# Clock.net
KiCad netlist of a schematic drawn in EAGLE
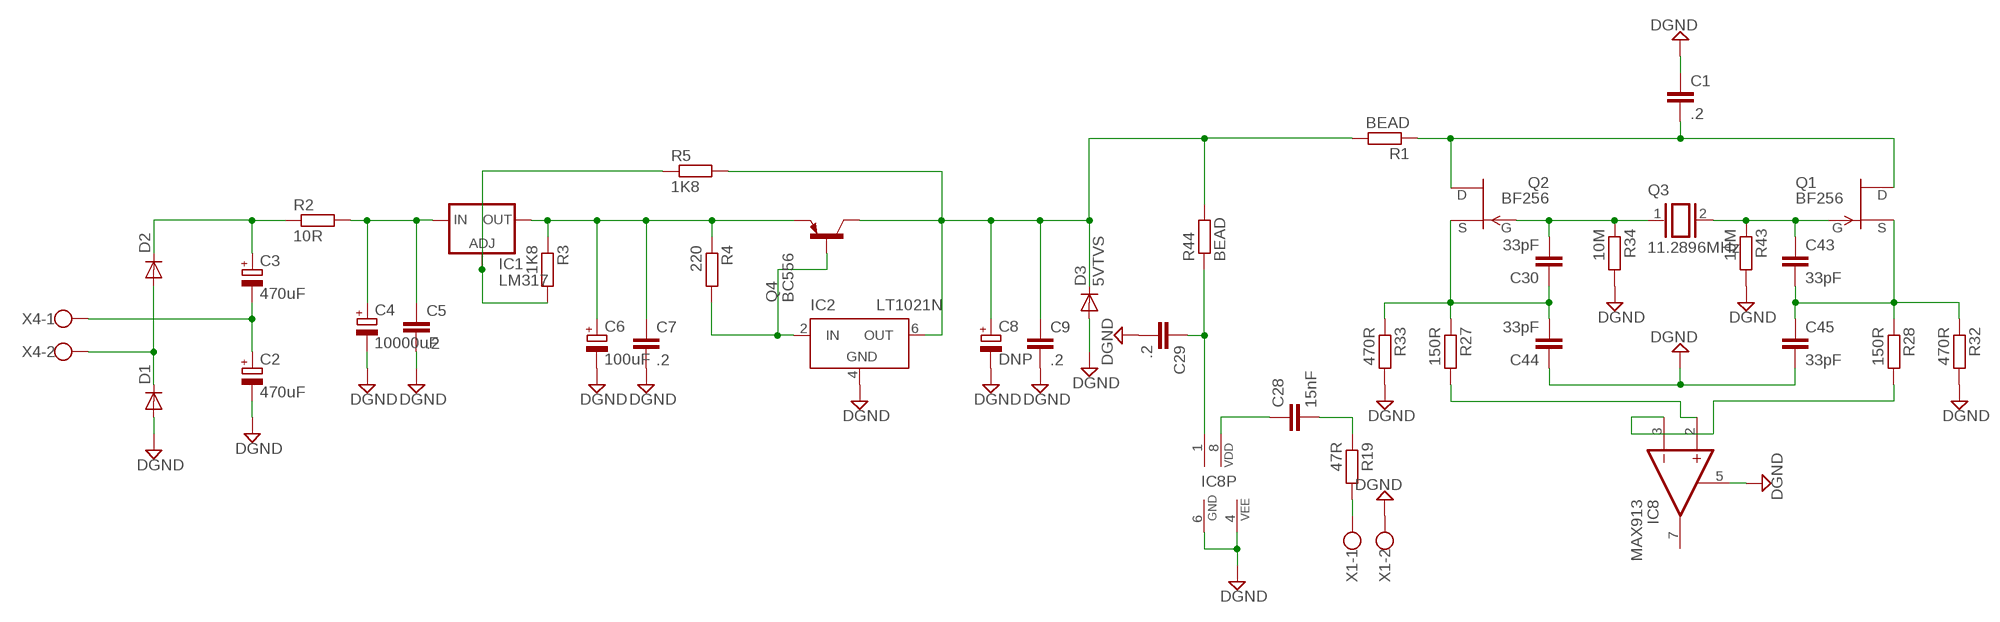
[diagram p0: schematic, sheet 1]

(export (version "E")
  (design (tool "Eeschema 10.0.6"))
  (components
    (comp (ref "C1")
      (value ".2")
      (footprint "eagle-import:C1210K")
      (libsource (lib "eagle-import") (part "C-EUC1210K"))
    )
    (comp (ref "C2")
      (value "470uF")
      (footprint "eagle-import:E5-10,5")
      (libsource (lib "eagle-import") (part "CPOL-EUE5-10.5"))
    )
    (comp (ref "C3")
      (value "470uF")
      (footprint "eagle-import:E5-10,5")
      (libsource (lib "eagle-import") (part "CPOL-EUE5-10.5"))
    )
    (comp (ref "C4")
      (value "10000uF")
      (footprint "eagle-import:E7,5-16")
      (libsource (lib "eagle-import") (part "CPOL-EUE7.5-16"))
    )
    (comp (ref "C5")
      (value ".2")
      (footprint "eagle-import:C1210K")
      (libsource (lib "eagle-import") (part "C-EUC1210K"))
    )
    (comp (ref "C6")
      (value "100uF")
      (footprint "eagle-import:E3,5-8")
      (libsource (lib "eagle-import") (part "CPOL-EUE3.5-8"))
    )
    (comp (ref "C7")
      (value ".2")
      (footprint "eagle-import:C1210K")
      (libsource (lib "eagle-import") (part "C-EUC1210K"))
    )
    (comp (ref "C8")
      (value "DNP")
      (footprint "eagle-import:E3,5-8")
      (libsource (lib "eagle-import") (part "CPOL-EUE3.5-8"))
    )
    (comp (ref "C9")
      (value ".2")
      (footprint "eagle-import:C1210K")
      (libsource (lib "eagle-import") (part "C-EUC1210K"))
    )
    (comp (ref "C28")
      (value "15nF")
      (footprint "eagle-import:C050-055X075")
      (libsource (lib "eagle-import") (part "C-EU050-055X075"))
    )
    (comp (ref "C29")
      (value ".2")
      (footprint "eagle-import:C1210K")
      (libsource (lib "eagle-import") (part "C-EUC1210K"))
    )
    (comp (ref "C30")
      (value "33pF")
      (footprint "eagle-import:C050-030X075")
      (libsource (lib "eagle-import") (part "C-EU050-030X075"))
    )
    (comp (ref "C43")
      (value "33pF")
      (footprint "eagle-import:C050-030X075")
      (libsource (lib "eagle-import") (part "C-EU050-030X075"))
    )
    (comp (ref "C44")
      (value "33pF")
      (footprint "eagle-import:C050-030X075")
      (libsource (lib "eagle-import") (part "C-EU050-030X075"))
    )
    (comp (ref "C45")
      (value "33pF")
      (footprint "eagle-import:C050-030X075")
      (libsource (lib "eagle-import") (part "C-EU050-030X075"))
    )
    (comp (ref "D1")
      (value "1N4148DO35-7")
      (footprint "eagle-import:DO35-7")
      (libsource (lib "eagle-import") (part "1N4148DO35-7"))
    )
    (comp (ref "D2")
      (value "1N4148DO35-7")
      (footprint "eagle-import:DO35-7")
      (libsource (lib "eagle-import") (part "1N4148DO35-7"))
    )
    (comp (ref "D3")
      (value "5VTVS")
      (footprint "eagle-import:DO204-10")
      (libsource (lib "eagle-import") (part "A114"))
    )
    (comp (ref "IC1")
      (value "LM317")
      (footprint "eagle-import:317TS")
      (libsource (lib "eagle-import") (part "LM317TS"))
    )
    (comp (ref "IC2")
      (value "LT1021N")
      (footprint "eagle-import:DIL08")
      (libsource (lib "eagle-import") (part "LT1021N"))
    )
    (comp (ref "IC8")
      (value "MAX913")
      (footprint "eagle-import:DIL08")
      (libsource (lib "eagle-import") (part "MAX903CPA"))
    )
    (comp (ref "Q1")
      (value "BF256")
      (footprint "eagle-import:TO92-")
      (libsource (lib "eagle-import") (part "?5482N4"))
    )
    (comp (ref "Q2")
      (value "BF256")
      (footprint "eagle-import:TO92-")
      (libsource (lib "eagle-import") (part "?5482N4"))
    )
    (comp (ref "Q3")
      (value "11.2896MHz")
      (footprint "eagle-import:QS")
      (libsource (lib "eagle-import") (part "XTAL/S"))
    )
    (comp (ref "Q4")
      (value "BC556")
      (footprint "eagle-import:TO92-EBC")
      (libsource (lib "eagle-import") (part "BC556"))
    )
    (comp (ref "R1")
      (value "BEAD")
      (footprint "eagle-import:R1210")
      (libsource (lib "eagle-import") (part "R-EU_R1210"))
    )
    (comp (ref "R2")
      (value "10R")
      (footprint "eagle-import:0207_10")
      (libsource (lib "eagle-import") (part "R-EU_0207/10"))
    )
    (comp (ref "R3")
      (value "1K8")
      (footprint "eagle-import:0204_7")
      (libsource (lib "eagle-import") (part "R-EU_0204/7"))
    )
    (comp (ref "R4")
      (value "220")
      (footprint "eagle-import:0204_7")
      (libsource (lib "eagle-import") (part "R-EU_0204/7"))
    )
    (comp (ref "R5")
      (value "1K8")
      (footprint "eagle-import:0204_7")
      (libsource (lib "eagle-import") (part "R-EU_0204/7"))
    )
    (comp (ref "R19")
      (value "47R")
      (footprint "eagle-import:R1210")
      (libsource (lib "eagle-import") (part "R-EU_R1210"))
    )
    (comp (ref "R27")
      (value "150R")
      (footprint "eagle-import:0204_7")
      (libsource (lib "eagle-import") (part "R-EU_0204/7"))
    )
    (comp (ref "R28")
      (value "150R")
      (footprint "eagle-import:0204_7")
      (libsource (lib "eagle-import") (part "R-EU_0204/7"))
    )
    (comp (ref "R32")
      (value "470R")
      (footprint "eagle-import:0204_7")
      (libsource (lib "eagle-import") (part "R-EU_0204/7"))
    )
    (comp (ref "R33")
      (value "470R")
      (footprint "eagle-import:0204_7")
      (libsource (lib "eagle-import") (part "R-EU_0204/7"))
    )
    (comp (ref "R34")
      (value "10M")
      (footprint "eagle-import:0204_7")
      (libsource (lib "eagle-import") (part "R-EU_0204/7"))
    )
    (comp (ref "R43")
      (value "10M")
      (footprint "eagle-import:0204_7")
      (libsource (lib "eagle-import") (part "R-EU_0204/7"))
    )
    (comp (ref "R44")
      (value "BEAD")
      (footprint "eagle-import:R1210")
      (libsource (lib "eagle-import") (part "R-EU_R1210"))
    )
    (comp (ref "X1")
      (value "W237-02P")
      (footprint "eagle-import:W237-132")
      (libsource (lib "eagle-import") (part "W237-02P"))
    )
    (comp (ref "X4")
      (value "W237-02P")
      (footprint "eagle-import:W237-132")
      (libsource (lib "eagle-import") (part "W237-02P"))
    )
  )
  (nets
    (net (code "1") (name "DGND") (class "Default")
      (node (ref "C1") (pin "1") (pinfunction "1_1") (pintype "passive"))
      (node (ref "C2") (pin "-") (pinfunction "-_-") (pintype "passive"))
      (node (ref "C29") (pin "2") (pinfunction "2_2") (pintype "passive"))
      (node (ref "C4") (pin "-") (pinfunction "-_-") (pintype "passive"))
      (node (ref "C44") (pin "1") (pinfunction "1_1") (pintype "passive"))
      (node (ref "C45") (pin "2") (pinfunction "2_2") (pintype "passive"))
      (node (ref "C5") (pin "2") (pinfunction "2_2") (pintype "passive"))
      (node (ref "C6") (pin "-") (pinfunction "-_-") (pintype "passive"))
      (node (ref "C7") (pin "2") (pinfunction "2_2") (pintype "passive"))
      (node (ref "C8") (pin "-") (pinfunction "-_-") (pintype "passive"))
      (node (ref "C9") (pin "2") (pinfunction "2_2") (pintype "passive"))
      (node (ref "D1") (pin "A") (pinfunction "A_A") (pintype "passive"))
      (node (ref "D3") (pin "A") (pinfunction "A_A") (pintype "passive"))
      (node (ref "IC2") (pin "4") (pinfunction "GND_4") (pintype "power_in"))
      (node (ref "IC8") (pin "4") (pinfunction "VEE_4") (pintype "power_in"))
      (node (ref "IC8") (pin "5") (pinfunction "LATCH_5") (pintype "passive"))
      (node (ref "IC8") (pin "6") (pinfunction "GND_6") (pintype "power_in"))
      (node (ref "R32") (pin "2") (pinfunction "2_2") (pintype "passive"))
      (node (ref "R33") (pin "2") (pinfunction "2_2") (pintype "passive"))
      (node (ref "R34") (pin "2") (pinfunction "2_2") (pintype "passive"))
      (node (ref "R43") (pin "2") (pinfunction "2_2") (pintype "passive"))
      (node (ref "X1") (pin "2") (pinfunction "KL_2") (pintype "passive"))
    )
    (net (code "2") (name "Net-(C3-Pad+)") (class "Default")
      (node (ref "C3") (pin "+") (pinfunction "+_+") (pintype "passive"))
      (node (ref "D2") (pin "C") (pinfunction "C_C") (pintype "passive"))
      (node (ref "R2") (pin "1") (pinfunction "1_1") (pintype "passive"))
    )
    (net (code "3") (name "Net-(C28-Pad2)") (class "Default")
      (node (ref "C28") (pin "2") (pinfunction "2_2") (pintype "passive"))
      (node (ref "R19") (pin "1") (pinfunction "1_1") (pintype "passive"))
    )
    (net (code "4") (name "Net-(IC1-ADJ)") (class "Default")
      (node (ref "IC1") (pin "1") (pinfunction "ADJ_1") (pintype "input"))
      (node (ref "R3") (pin "2") (pinfunction "2_2") (pintype "passive"))
      (node (ref "R5") (pin "1") (pinfunction "1_1") (pintype "passive"))
    )
    (net (code "5") (name "Net-(IC1-IN)") (class "Default")
      (node (ref "C4") (pin "+") (pinfunction "+_+") (pintype "passive"))
      (node (ref "C5") (pin "1") (pinfunction "1_1") (pintype "passive"))
      (node (ref "IC1") (pin "3") (pinfunction "IN_3") (pintype "input"))
      (node (ref "R2") (pin "2") (pinfunction "2_2") (pintype "passive"))
    )
    (net (code "6") (name "Net-(IC1-OUT)") (class "Default")
      (node (ref "C6") (pin "+") (pinfunction "+_+") (pintype "passive"))
      (node (ref "C7") (pin "1") (pinfunction "1_1") (pintype "passive"))
      (node (ref "IC1") (pin "2") (pinfunction "OUT_2") (pintype "passive"))
      (node (ref "Q4") (pin "E") (pinfunction "E_E") (pintype "passive"))
      (node (ref "R3") (pin "1") (pinfunction "1_1") (pintype "passive"))
      (node (ref "R4") (pin "1") (pinfunction "1_1") (pintype "passive"))
    )
    (net (code "7") (name "Net-(IC2-IN)") (class "Default")
      (node (ref "IC2") (pin "2") (pinfunction "IN_2") (pintype "input"))
      (node (ref "Q4") (pin "B") (pinfunction "B_B") (pintype "passive"))
      (node (ref "R4") (pin "2") (pinfunction "2_2") (pintype "passive"))
    )
    (net (code "8") (name "Net-(IC2-OUT)") (class "Default")
      (node (ref "C8") (pin "+") (pinfunction "+_+") (pintype "passive"))
      (node (ref "C9") (pin "1") (pinfunction "1_1") (pintype "passive"))
      (node (ref "D3") (pin "C") (pinfunction "C_C") (pintype "passive"))
      (node (ref "IC2") (pin "6") (pinfunction "OUT_6") (pintype "output"))
      (node (ref "Q4") (pin "C") (pinfunction "C_C") (pintype "passive"))
      (node (ref "R1") (pin "2") (pinfunction "2_2") (pintype "passive"))
      (node (ref "R44") (pin "2") (pinfunction "2_2") (pintype "passive"))
      (node (ref "R5") (pin "2") (pinfunction "2_2") (pintype "passive"))
    )
    (net (code "9") (name "Net-(IC8A-+IN)") (class "Default")
      (node (ref "IC8") (pin "2") (pinfunction "+IN_2") (pintype "input"))
      (node (ref "R27") (pin "2") (pinfunction "2_2") (pintype "passive"))
    )
    (net (code "10") (name "Net-(IC8A--IN)") (class "Default")
      (node (ref "IC8") (pin "3") (pinfunction "-IN_3") (pintype "input"))
      (node (ref "R28") (pin "2") (pinfunction "2_2") (pintype "passive"))
    )
    (net (code "11") (name "Net-(IC8B-VCC)") (class "Default")
      (node (ref "C29") (pin "1") (pinfunction "1_1") (pintype "passive"))
      (node (ref "IC8") (pin "1") (pinfunction "VCC_1") (pintype "power_in"))
      (node (ref "R44") (pin "1") (pinfunction "1_1") (pintype "passive"))
    )
    (net (code "12") (name "Net-(IC8B-VDD)") (class "Default")
      (node (ref "C28") (pin "1") (pinfunction "1_1") (pintype "passive"))
      (node (ref "IC8") (pin "8") (pinfunction "VDD_8") (pintype "power_in"))
    )
    (net (code "13") (name "Net-(Q1-D)") (class "Default")
      (node (ref "C1") (pin "2") (pinfunction "2_2") (pintype "passive"))
      (node (ref "Q1") (pin "3") (pinfunction "D_3") (pintype "passive"))
      (node (ref "Q2") (pin "3") (pinfunction "D_3") (pintype "passive"))
      (node (ref "R1") (pin "1") (pinfunction "1_1") (pintype "passive"))
    )
    (net (code "14") (name "Net-(Q1-G)") (class "Default")
      (node (ref "C43") (pin "1") (pinfunction "1_1") (pintype "passive"))
      (node (ref "Q1") (pin "1") (pinfunction "G_1") (pintype "passive"))
      (node (ref "Q3") (pin "2") (pinfunction "2_2") (pintype "passive"))
      (node (ref "R43") (pin "1") (pinfunction "1_1") (pintype "passive"))
    )
    (net (code "15") (name "Net-(Q1-S)") (class "Default")
      (node (ref "C43") (pin "2") (pinfunction "2_2") (pintype "passive"))
      (node (ref "C45") (pin "1") (pinfunction "1_1") (pintype "passive"))
      (node (ref "Q1") (pin "2") (pinfunction "S_2") (pintype "passive"))
      (node (ref "R28") (pin "1") (pinfunction "1_1") (pintype "passive"))
      (node (ref "R32") (pin "1") (pinfunction "1_1") (pintype "passive"))
    )
    (net (code "16") (name "Net-(Q2-G)") (class "Default")
      (node (ref "C30") (pin "2") (pinfunction "2_2") (pintype "passive"))
      (node (ref "Q2") (pin "1") (pinfunction "G_1") (pintype "passive"))
      (node (ref "Q3") (pin "1") (pinfunction "1_1") (pintype "passive"))
      (node (ref "R34") (pin "1") (pinfunction "1_1") (pintype "passive"))
    )
    (net (code "17") (name "Net-(Q2-S)") (class "Default")
      (node (ref "C30") (pin "1") (pinfunction "1_1") (pintype "passive"))
      (node (ref "C44") (pin "2") (pinfunction "2_2") (pintype "passive"))
      (node (ref "Q2") (pin "2") (pinfunction "S_2") (pintype "passive"))
      (node (ref "R27") (pin "1") (pinfunction "1_1") (pintype "passive"))
      (node (ref "R33") (pin "1") (pinfunction "1_1") (pintype "passive"))
    )
    (net (code "18") (name "Net-(X1A-KL)") (class "Default")
      (node (ref "R19") (pin "2") (pinfunction "2_2") (pintype "passive"))
      (node (ref "X1") (pin "1") (pinfunction "KL_1") (pintype "passive"))
    )
    (net (code "19") (name "Net-(X4A-KL)") (class "Default")
      (node (ref "C2") (pin "+") (pinfunction "+_+") (pintype "passive"))
      (node (ref "C3") (pin "-") (pinfunction "-_-") (pintype "passive"))
      (node (ref "X4") (pin "1") (pinfunction "KL_1") (pintype "passive"))
    )
    (net (code "20") (name "Net-(X4B-KL)") (class "Default")
      (node (ref "D1") (pin "C") (pinfunction "C_C") (pintype "passive"))
      (node (ref "D2") (pin "A") (pinfunction "A_A") (pintype "passive"))
      (node (ref "X4") (pin "2") (pinfunction "KL_2") (pintype "passive"))
    )
    (net (code "21") (name "unconnected-(IC8A-OUT-Pad7)") (class "Default")
      (node (ref "IC8") (pin "7") (pinfunction "OUT_7") (pintype "output"))
    )
  )
)
